# ESP32.net
KiCad netlist of a schematic drawn in Altium Designer
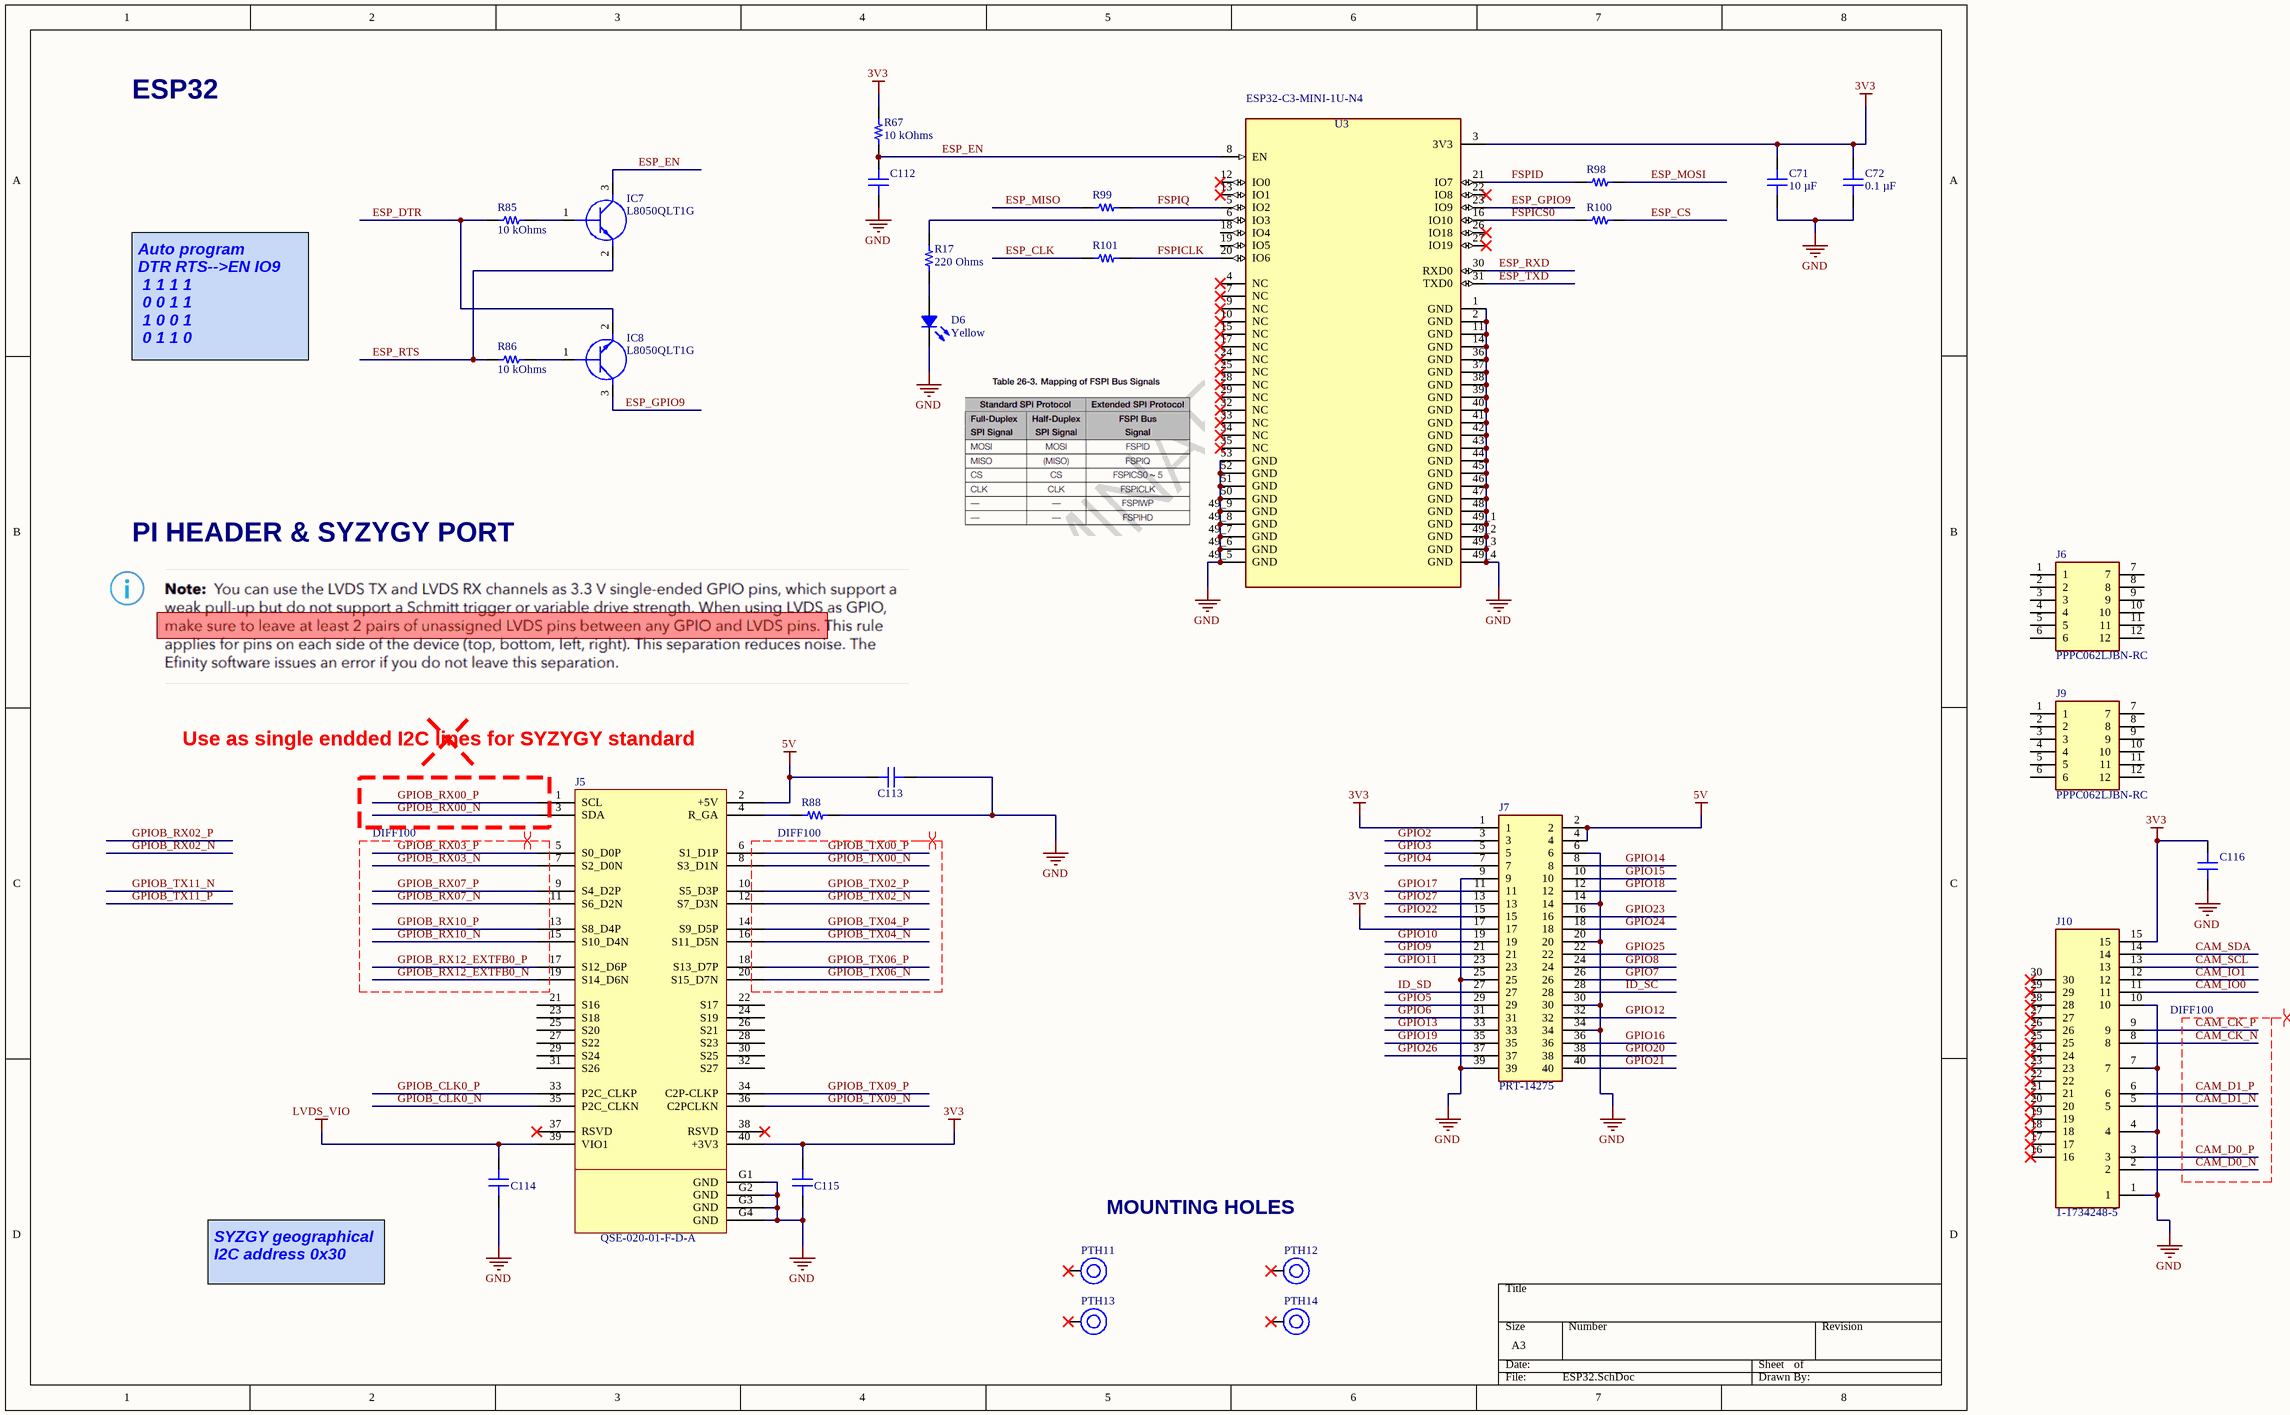
[diagram p0: ESP32.SchDoc]

(export (version "E")
  (design (tool "Eeschema 10.0.6"))
  (components
    (comp (ref "C71")
      (value "10 µF")
      (footprint "CAP 0603_1608")
      (description "CAP CER 10UF 6.3V X5R 0603")
      (fields
        (field (name "PART NUMBER") "GRM188R60J106ME47D")
        (field (name "MANUFACTURER") "Murata Electronics")
      )
      (libsource (lib "Celestial Altium Library - altium_library") (part "Capacitor"))
    )
    (comp (ref "C72")
      (value "0.1 µF")
      (footprint "CAP 0603_1608")
      (description "CAP CER 0.1UF 6.3V X7R 0603")
      (fields
        (field (name "PART NUMBER") "6R3X14W104MV4T")
        (field (name "MANUFACTURER") "Johanson Dielectrics Inc.")
      )
      (libsource (lib "Celestial Altium Library - altium_library") (part "Capacitor"))
    )
    (comp (ref "C112")
      (value "1 µF")
      (footprint "CAP 0402_1005")
      (description "CAP CER 1UF 6.3V X7R 0402")
      (fields
        (field (name "PART NUMBER") "GRM155R70J105KA12J")
        (field (name "MANUFACTURER") "Murata Electronics")
      )
      (libsource (lib "Celestial Altium Library - altium_library") (part "Capacitor"))
    )
    (comp (ref "C113")
      (value "0.1 µF")
      (footprint "CAP 0402_1005")
      (description "CAP CER 0.1UF 10V X7R 0402")
      (fields (field (name "PART NUMBER") "CC0402KRX7R6BB104") (field (name "MANUFACTURER") "Yageo"))
      (libsource (lib "Celestial Altium Library - altium_library") (part "Capacitor"))
    )
    (comp (ref "C114")
      (value "0.1 µF")
      (footprint "CAP 0402_1005")
      (description "CAP CER 0.1UF 10V X7R 0402")
      (fields (field (name "PART NUMBER") "CC0402KRX7R6BB104") (field (name "MANUFACTURER") "Yageo"))
      (libsource (lib "Celestial Altium Library - altium_library") (part "Capacitor"))
    )
    (comp (ref "C115")
      (value "0.1 µF")
      (footprint "CAP 0402_1005")
      (description "CAP CER 0.1UF 10V X7R 0402")
      (fields (field (name "PART NUMBER") "CC0402KRX7R6BB104") (field (name "MANUFACTURER") "Yageo"))
      (libsource (lib "Celestial Altium Library - altium_library") (part "Capacitor"))
    )
    (comp (ref "C116")
      (value "0.1 µF")
      (footprint "CAP 0402_1005")
      (description "CAP CER 0.1UF 10V X7R 0402")
      (fields (field (name "PART NUMBER") "CC0402KRX7R6BB104") (field (name "MANUFACTURER") "Yageo"))
      (libsource (lib "Celestial Altium Library - altium_library") (part "Capacitor"))
    )
    (comp (ref "D6")
      (value "Yellow")
      (footprint "LED 0603_1608 YELLOW")
      (description "LED YELLOW DIFFUSED SMD")
      (fields
        (field (name "PART NUMBER") "SML-LX0603YW-TR")
        (field (name "MANUFACTURER") "Lumex Opto/Components Inc.")
      )
      (libsource (lib "Celestial Altium Library - altium_library") (part "LED"))
    )
    (comp (ref "IC7")
      (value "L8050QLT1G")
      (footprint "SamacSys:L8050QLT1G")
      (description "Integrated Circuit")
      (libsource (lib "SamacSys") (part "L8050QLT1G"))
    )
    (comp (ref "IC8")
      (value "L8050QLT1G")
      (footprint "SamacSys:L8050QLT1G")
      (description "Integrated Circuit")
      (libsource (lib "SamacSys") (part "L8050QLT1G"))
    )
    (comp (ref "J5")
      (value "QSE-020-01-F-D-A")
      (footprint "Components - 26.11.22 - 19.48:QSE-020-01-F-D-A-Footprint-2")
      (description "Conn High Speed Socket Strip SKT 40 POS 0.8mm Solder ST SMD Tray")
      (libsource (lib "Components - 26.11.22 - 19.48") (part "CMP-002-00073-2_2"))
    )
    (comp (ref "J6")
      (value "PPPC062LJBN-RC")
      (footprint "SamacSys:RHDRRA12W60P254X254_2X6_1574X850X508P")
      (description "Connector")
      (libsource (lib "SamacSys") (part "PPPC062LJBN-RC"))
    )
    (comp (ref "J7")
      (value "PRT-14275")
      (footprint "SamacSys:HDRV40W64P254_2X20_5080X500X884P")
      (description "Connector")
      (fields (field (name "MOUSER PART NUMBER") "474-PRT-14275"))
      (libsource (lib "SamacSys") (part "PRT-14275"))
    )
    (comp (ref "J9")
      (value "PPPC062LJBN-RC")
      (footprint "SamacSys:RHDRRA12W60P254X254_2X6_1574X850X508P")
      (description "Connector")
      (libsource (lib "SamacSys") (part "PPPC062LJBN-RC"))
    )
    (comp (ref "J10")
      (value "1-1734248-5")
      (footprint "SamacSys:117342485")
      (description "Connector")
      (fields (field (name "MOUSER PART NUMBER") "571-1-1734248-5"))
      (libsource (lib "SamacSys") (part "1-1734248-5"))
    )
    (comp (ref "PTH11")
      (value "SYZYGY_PCB_Mounting_Hole")
      (footprint "SYZYGY_PCB_Mounting_Hole")
      (libsource (lib "T8_devkit_PCB") (part "SYZYGY_PCB_Mounting_Hole"))
    )
    (comp (ref "PTH12")
      (value "SYZYGY_PCB_Mounting_Hole")
      (footprint "SYZYGY_PCB_Mounting_Hole")
      (libsource (lib "T8_devkit_PCB") (part "SYZYGY_PCB_Mounting_Hole"))
    )
    (comp (ref "PTH13")
      (value "SYZYGY_PCB_Mounting_Hole")
      (footprint "SYZYGY_PCB_Mounting_Hole")
      (libsource (lib "T8_devkit_PCB") (part "SYZYGY_PCB_Mounting_Hole"))
    )
    (comp (ref "PTH14")
      (value "SYZYGY_PCB_Mounting_Hole")
      (footprint "SYZYGY_PCB_Mounting_Hole")
      (libsource (lib "T8_devkit_PCB") (part "SYZYGY_PCB_Mounting_Hole"))
    )
    (comp (ref "R17")
      (value "220 Ohms")
      (footprint "RES 0402_1005")
      (description "RES 220 OHM 1% 1/16W 0402")
      (fields (field (name "PART NUMBER") "RC0402FR-07220RL") (field (name "MANUFACTURER") "Yageo"))
      (libsource (lib "Celestial Altium Library - altium_library") (part "Resistor"))
    )
    (comp (ref "R67")
      (value "10 kOhms")
      (footprint "RES 0402_1005")
      (description "RES 10K OHM 0.1% 1/10W 0402")
      (fields
        (field (name "PART NUMBER") "RP73PF1E10KBTD")
        (field (name "MANUFACTURER") "TE Connectivity Passive Product")
      )
      (libsource (lib "Celestial Altium Library - altium_library") (part "Resistor"))
    )
    (comp (ref "R85")
      (value "10 kOhms")
      (footprint "RES 0402_1005")
      (description "RES 10K OHM 0.1% 1/10W 0402")
      (fields
        (field (name "PART NUMBER") "RP73PF1E10KBTD")
        (field (name "MANUFACTURER") "TE Connectivity Passive Product")
      )
      (libsource (lib "Celestial Altium Library - altium_library") (part "Resistor"))
    )
    (comp (ref "R86")
      (value "10 kOhms")
      (footprint "RES 0402_1005")
      (description "RES 10K OHM 0.1% 1/10W 0402")
      (fields
        (field (name "PART NUMBER") "RP73PF1E10KBTD")
        (field (name "MANUFACTURER") "TE Connectivity Passive Product")
      )
      (libsource (lib "Celestial Altium Library - altium_library") (part "Resistor"))
    )
    (comp (ref "R88")
      (value "210 kOhms")
      (footprint "RES 0402_1005")
      (description "RES 210K OHM 1% 1/16W 0402")
      (fields (field (name "PART NUMBER") "RC0402FR-07210KL") (field (name "MANUFACTURER") "Yageo"))
      (libsource (lib "Celestial Altium Library - altium_library") (part "Resistor"))
    )
    (comp (ref "R98")
      (value "33 Ohms")
      (footprint "RES 0402_1005")
      (description "RES 33 OHM 1% 1/16W 0402")
      (fields (field (name "PART NUMBER") "RC0402FR-0733RL") (field (name "MANUFACTURER") "Yageo"))
      (libsource (lib "Celestial Altium Library - altium_library") (part "Resistor"))
    )
    (comp (ref "R99")
      (value "33 Ohms")
      (footprint "RES 0402_1005")
      (description "RES 33 OHM 1% 1/16W 0402")
      (fields (field (name "PART NUMBER") "RC0402FR-0733RL") (field (name "MANUFACTURER") "Yageo"))
      (libsource (lib "Celestial Altium Library - altium_library") (part "Resistor"))
    )
    (comp (ref "R100")
      (value "33 Ohms")
      (footprint "RES 0402_1005")
      (description "RES 33 OHM 1% 1/16W 0402")
      (fields (field (name "PART NUMBER") "RC0402FR-0733RL") (field (name "MANUFACTURER") "Yageo"))
      (libsource (lib "Celestial Altium Library - altium_library") (part "Resistor"))
    )
    (comp (ref "R101")
      (value "33 Ohms")
      (footprint "RES 0402_1005")
      (description "RES 33 OHM 1% 1/16W 0402")
      (fields (field (name "PART NUMBER") "RC0402FR-0733RL") (field (name "MANUFACTURER") "Yageo"))
      (libsource (lib "Celestial Altium Library - altium_library") (part "Resistor"))
    )
    (comp (ref "U3")
      (value "ESP32-C3-MINI-1U-N4")
      (footprint "XCVR_ESP32-C3-MINI-1U-N4:XCVR_ESP32-C3-MINI-1U-N4")
      (fields
        (field (name "MF") "Espressif Systems")
        (field (name "DIGI-KEY_PART_NUMBER") "1965-ESP32-C3-MINI-1U-N4TR-ND")
      )
      (libsource (lib "ESP32-C3-MINI-1U-N4") (part "ESP32-C3-MINI-1U-N4"))
    )
  )
  (nets
    (net (code "1") (name "/CAM_CK_N") (class "Default")
      (node (ref "J10") (pin "8") (pinfunction "8_8") (pintype "passive"))
    )
    (net (code "2") (name "/CAM_CK_P") (class "Default")
      (node (ref "J10") (pin "9") (pinfunction "9_9") (pintype "passive"))
    )
    (net (code "3") (name "/CAM_D0_N") (class "Default")
      (node (ref "J10") (pin "2") (pinfunction "2_2") (pintype "passive"))
    )
    (net (code "4") (name "/CAM_D0_P") (class "Default")
      (node (ref "J10") (pin "3") (pinfunction "3_3") (pintype "passive"))
    )
    (net (code "5") (name "/CAM_D1_N") (class "Default")
      (node (ref "J10") (pin "5") (pinfunction "5_5") (pintype "passive"))
    )
    (net (code "6") (name "/CAM_D1_P") (class "Default")
      (node (ref "J10") (pin "6") (pinfunction "6_6") (pintype "passive"))
    )
    (net (code "7") (name "/CAM_IO0") (class "Default")
      (node (ref "J10") (pin "11") (pinfunction "11_11") (pintype "passive"))
    )
    (net (code "8") (name "/CAM_IO1") (class "Default")
      (node (ref "J10") (pin "12") (pinfunction "12_12") (pintype "passive"))
    )
    (net (code "9") (name "/CAM_SCL") (class "Default")
      (node (ref "J10") (pin "13") (pinfunction "13_13") (pintype "passive"))
    )
    (net (code "10") (name "/CAM_SDA") (class "Default")
      (node (ref "J10") (pin "14") (pinfunction "14_14") (pintype "passive"))
    )
    (net (code "11") (name "/ESP_CLK") (class "Default")
      (node (ref "R101") (pin "1") (pinfunction "1_1") (pintype "passive"))
    )
    (net (code "12") (name "/ESP_CS") (class "Default")
      (node (ref "R100") (pin "2") (pinfunction "2_2") (pintype "passive"))
    )
    (net (code "13") (name "/ESP_DTR") (class "Default")
      (node (ref "IC8") (pin "2") (pinfunction "E_2") (pintype "passive"))
      (node (ref "R85") (pin "2") (pinfunction "2_2") (pintype "passive"))
    )
    (net (code "14") (name "/ESP_EN") (class "Default")
      (node (ref "C112") (pin "2") (pinfunction "2_2") (pintype "passive"))
      (node (ref "IC7") (pin "3") (pinfunction "C_3") (pintype "passive"))
      (node (ref "R67") (pin "1") (pinfunction "1_1") (pintype "passive"))
      (node (ref "U3") (pin "8") (pinfunction "EN_8") (pintype "input"))
    )
    (net (code "15") (name "/ESP_GPIO9") (class "Default")
      (node (ref "IC8") (pin "3") (pinfunction "C_3") (pintype "passive"))
      (node (ref "U3") (pin "23") (pinfunction "IO9_23") (pintype "bidirectional"))
    )
    (net (code "16") (name "/ESP_MISO") (class "Default")
      (node (ref "R99") (pin "1") (pinfunction "1_1") (pintype "passive"))
    )
    (net (code "17") (name "/ESP_MOSI") (class "Default")
      (node (ref "R98") (pin "2") (pinfunction "2_2") (pintype "passive"))
    )
    (net (code "18") (name "/ESP_RTS") (class "Default")
      (node (ref "IC7") (pin "2") (pinfunction "E_2") (pintype "passive"))
      (node (ref "R86") (pin "2") (pinfunction "2_2") (pintype "passive"))
    )
    (net (code "19") (name "/ESP_RXD") (class "Default")
      (node (ref "U3") (pin "30") (pinfunction "RXD0_30") (pintype "bidirectional"))
    )
    (net (code "20") (name "/ESP_TXD") (class "Default")
      (node (ref "U3") (pin "31") (pinfunction "TXD0_31") (pintype "bidirectional"))
    )
    (net (code "21") (name "/FSPICLK") (class "Default")
      (node (ref "R101") (pin "2") (pinfunction "2_2") (pintype "passive"))
      (node (ref "U3") (pin "20") (pinfunction "IO6_20") (pintype "bidirectional"))
    )
    (net (code "22") (name "/FSPICS0") (class "Default")
      (node (ref "R100") (pin "1") (pinfunction "1_1") (pintype "passive"))
      (node (ref "U3") (pin "16") (pinfunction "IO10_16") (pintype "bidirectional"))
    )
    (net (code "23") (name "/FSPID") (class "Default")
      (node (ref "R98") (pin "1") (pinfunction "1_1") (pintype "passive"))
      (node (ref "U3") (pin "21") (pinfunction "IO7_21") (pintype "bidirectional"))
    )
    (net (code "24") (name "/FSPIQ") (class "Default")
      (node (ref "R99") (pin "2") (pinfunction "2_2") (pintype "passive"))
      (node (ref "U3") (pin "5") (pinfunction "IO2_5") (pintype "bidirectional"))
    )
    (net (code "25") (name "/GPIO2") (class "Default")
      (node (ref "J7") (pin "3") (pinfunction "3_3") (pintype "passive"))
    )
    (net (code "26") (name "/GPIO3") (class "Default")
      (node (ref "J7") (pin "5") (pinfunction "5_5") (pintype "passive"))
    )
    (net (code "27") (name "/GPIO4") (class "Default")
      (node (ref "J7") (pin "7") (pinfunction "7_7") (pintype "passive"))
    )
    (net (code "28") (name "/GPIO5") (class "Default")
      (node (ref "J7") (pin "29") (pinfunction "29_29") (pintype "passive"))
    )
    (net (code "29") (name "/GPIO6") (class "Default")
      (node (ref "J7") (pin "31") (pinfunction "31_31") (pintype "passive"))
    )
    (net (code "30") (name "/GPIO7") (class "Default")
      (node (ref "J7") (pin "26") (pinfunction "26_26") (pintype "passive"))
    )
    (net (code "31") (name "/GPIO8") (class "Default")
      (node (ref "J7") (pin "24") (pinfunction "24_24") (pintype "passive"))
    )
    (net (code "32") (name "/GPIO9") (class "Default")
      (node (ref "J7") (pin "21") (pinfunction "21_21") (pintype "passive"))
    )
    (net (code "33") (name "/GPIO10") (class "Default")
      (node (ref "J7") (pin "19") (pinfunction "19_19") (pintype "passive"))
    )
    (net (code "34") (name "/GPIO11") (class "Default")
      (node (ref "J7") (pin "23") (pinfunction "23_23") (pintype "passive"))
    )
    (net (code "35") (name "/GPIO12") (class "Default")
      (node (ref "J7") (pin "32") (pinfunction "32_32") (pintype "passive"))
    )
    (net (code "36") (name "/GPIO13") (class "Default")
      (node (ref "J7") (pin "33") (pinfunction "33_33") (pintype "passive"))
    )
    (net (code "37") (name "/GPIO14") (class "Default")
      (node (ref "J7") (pin "8") (pinfunction "8_8") (pintype "passive"))
    )
    (net (code "38") (name "/GPIO15") (class "Default")
      (node (ref "J7") (pin "10") (pinfunction "10_10") (pintype "passive"))
    )
    (net (code "39") (name "/GPIO16") (class "Default")
      (node (ref "J7") (pin "36") (pinfunction "36_36") (pintype "passive"))
    )
    (net (code "40") (name "/GPIO17") (class "Default")
      (node (ref "J7") (pin "11") (pinfunction "11_11") (pintype "passive"))
    )
    (net (code "41") (name "/GPIO18") (class "Default")
      (node (ref "J7") (pin "12") (pinfunction "12_12") (pintype "passive"))
    )
    (net (code "42") (name "/GPIO19") (class "Default")
      (node (ref "J7") (pin "35") (pinfunction "35_35") (pintype "passive"))
    )
    (net (code "43") (name "/GPIO20") (class "Default")
      (node (ref "J7") (pin "38") (pinfunction "38_38") (pintype "passive"))
    )
    (net (code "44") (name "/GPIO21") (class "Default")
      (node (ref "J7") (pin "40") (pinfunction "40_40") (pintype "passive"))
    )
    (net (code "45") (name "/GPIO22") (class "Default")
      (node (ref "J7") (pin "15") (pinfunction "15_15") (pintype "passive"))
    )
    (net (code "46") (name "/GPIO23") (class "Default")
      (node (ref "J7") (pin "16") (pinfunction "16_16") (pintype "passive"))
    )
    (net (code "47") (name "/GPIO24") (class "Default")
      (node (ref "J7") (pin "18") (pinfunction "18_18") (pintype "passive"))
    )
    (net (code "48") (name "/GPIO25") (class "Default")
      (node (ref "J7") (pin "22") (pinfunction "22_22") (pintype "passive"))
    )
    (net (code "49") (name "/GPIO26") (class "Default")
      (node (ref "J7") (pin "37") (pinfunction "37_37") (pintype "passive"))
    )
    (net (code "50") (name "/GPIO27") (class "Default")
      (node (ref "J7") (pin "13") (pinfunction "13_13") (pintype "passive"))
    )
    (net (code "51") (name "/GPIOB_CLK0_N") (class "Default")
      (node (ref "J5") (pin "35") (pinfunction "P2C_CLKN_35") (pintype "passive"))
    )
    (net (code "52") (name "/GPIOB_CLK0_P") (class "Default")
      (node (ref "J5") (pin "33") (pinfunction "P2C_CLKP_33") (pintype "passive"))
    )
    (net (code "53") (name "/GPIOB_RX00_N") (class "Default")
      (node (ref "J5") (pin "3") (pinfunction "SDA_3") (pintype "passive"))
    )
    (net (code "54") (name "/GPIOB_RX00_P") (class "Default")
      (node (ref "J5") (pin "1") (pinfunction "SCL_1") (pintype "passive"))
    )
    (net (code "57") (name "/GPIOB_RX03_N") (class "Default")
      (node (ref "J5") (pin "7") (pinfunction "S2_D0N_7") (pintype "passive"))
    )
    (net (code "58") (name "/GPIOB_RX03_P") (class "Default")
      (node (ref "J5") (pin "5") (pinfunction "S0_D0P_5") (pintype "passive"))
    )
    (net (code "59") (name "/GPIOB_RX07_N") (class "Default")
      (node (ref "J5") (pin "11") (pinfunction "S6_D2N_11") (pintype "passive"))
    )
    (net (code "60") (name "/GPIOB_RX07_P") (class "Default")
      (node (ref "J5") (pin "9") (pinfunction "S4_D2P_9") (pintype "passive"))
    )
    (net (code "61") (name "/GPIOB_RX10_N") (class "Default")
      (node (ref "J5") (pin "15") (pinfunction "S10_D4N_15") (pintype "passive"))
    )
    (net (code "62") (name "/GPIOB_RX10_P") (class "Default")
      (node (ref "J5") (pin "13") (pinfunction "S8_D4P_13") (pintype "passive"))
    )
    (net (code "63") (name "/GPIOB_RX12_EXTFB0_N") (class "Default")
      (node (ref "J5") (pin "19") (pinfunction "S14_D6N_19") (pintype "passive"))
    )
    (net (code "64") (name "/GPIOB_RX12_EXTFB0_P") (class "Default")
      (node (ref "J5") (pin "17") (pinfunction "S12_D6P_17") (pintype "passive"))
    )
    (net (code "65") (name "/GPIOB_TX00_N") (class "Default")
      (node (ref "J5") (pin "8") (pinfunction "S3_D1N_8") (pintype "passive"))
    )
    (net (code "66") (name "/GPIOB_TX00_P") (class "Default")
      (node (ref "J5") (pin "6") (pinfunction "S1_D1P_6") (pintype "passive"))
    )
    (net (code "67") (name "/GPIOB_TX02_N") (class "Default")
      (node (ref "J5") (pin "12") (pinfunction "S7_D3N_12") (pintype "passive"))
    )
    (net (code "68") (name "/GPIOB_TX02_P") (class "Default")
      (node (ref "J5") (pin "10") (pinfunction "S5_D3P_10") (pintype "passive"))
    )
    (net (code "69") (name "/GPIOB_TX04_N") (class "Default")
      (node (ref "J5") (pin "16") (pinfunction "S11_D5N_16") (pintype "passive"))
    )
    (net (code "70") (name "/GPIOB_TX04_P") (class "Default")
      (node (ref "J5") (pin "14") (pinfunction "S9_D5P_14") (pintype "passive"))
    )
    (net (code "71") (name "/GPIOB_TX06_N") (class "Default")
      (node (ref "J5") (pin "20") (pinfunction "S15_D7N_20") (pintype "passive"))
    )
    (net (code "72") (name "/GPIOB_TX06_P") (class "Default")
      (node (ref "J5") (pin "18") (pinfunction "S13_D7P_18") (pintype "passive"))
    )
    (net (code "73") (name "/GPIOB_TX09_N") (class "Default")
      (node (ref "J5") (pin "36") (pinfunction "C2PCLKN_36") (pintype "passive"))
    )
    (net (code "74") (name "/GPIOB_TX09_P") (class "Default")
      (node (ref "J5") (pin "34") (pinfunction "C2P-CLKP_34") (pintype "passive"))
    )
    (net (code "77") (name "/ID_SC") (class "Default")
      (node (ref "J7") (pin "28") (pinfunction "28_28") (pintype "passive"))
    )
    (net (code "78") (name "/ID_SD") (class "Default")
      (node (ref "J7") (pin "27") (pinfunction "27_27") (pintype "passive"))
    )
    (net (code "79") (name "3V3") (class "Default")
      (node (ref "C115") (pin "1") (pinfunction "1_1") (pintype "passive"))
      (node (ref "C116") (pin "2") (pinfunction "2_2") (pintype "passive"))
      (node (ref "C71") (pin "2") (pinfunction "2_2") (pintype "passive"))
      (node (ref "C72") (pin "2") (pinfunction "2_2") (pintype "passive"))
      (node (ref "J10") (pin "15") (pinfunction "15_15") (pintype "passive"))
      (node (ref "J5") (pin "40") (pinfunction "+3V3_40") (pintype "passive"))
      (node (ref "J7") (pin "1") (pinfunction "1_1") (pintype "passive"))
      (node (ref "J7") (pin "17") (pinfunction "17_17") (pintype "passive"))
      (node (ref "R67") (pin "2") (pinfunction "2_2") (pintype "passive"))
      (node (ref "U3") (pin "3") (pinfunction "3V3_3") (pintype "power_in"))
    )
    (net (code "80") (name "5V") (class "Default")
      (node (ref "C113") (pin "2") (pinfunction "2_2") (pintype "passive"))
      (node (ref "J5") (pin "2") (pinfunction "+5V_2") (pintype "passive"))
      (node (ref "J7") (pin "2") (pinfunction "2_2") (pintype "passive"))
      (node (ref "J7") (pin "4") (pinfunction "4_4") (pintype "passive"))
    )
    (net (code "81") (name "GND") (class "Default")
      (node (ref "C112") (pin "1") (pinfunction "1_1") (pintype "passive"))
      (node (ref "C113") (pin "1") (pinfunction "1_1") (pintype "passive"))
      (node (ref "C114") (pin "2") (pinfunction "2_2") (pintype "passive"))
      (node (ref "C115") (pin "2") (pinfunction "2_2") (pintype "passive"))
      (node (ref "C116") (pin "1") (pinfunction "1_1") (pintype "passive"))
      (node (ref "C71") (pin "1") (pinfunction "1_1") (pintype "passive"))
      (node (ref "C72") (pin "1") (pinfunction "1_1") (pintype "passive"))
      (node (ref "D6") (pin "2") (pinfunction "2_2") (pintype "passive"))
      (node (ref "J10") (pin "1") (pinfunction "1_1") (pintype "passive"))
      (node (ref "J10") (pin "10") (pinfunction "10_10") (pintype "passive"))
      (node (ref "J10") (pin "4") (pinfunction "4_4") (pintype "passive"))
      (node (ref "J10") (pin "7") (pinfunction "7_7") (pintype "passive"))
      (node (ref "J5") (pin "G1") (pinfunction "GND_G1") (pintype "power_in"))
      (node (ref "J5") (pin "G2") (pinfunction "GND_G2") (pintype "power_in"))
      (node (ref "J5") (pin "G3") (pinfunction "GND_G3") (pintype "power_in"))
      (node (ref "J5") (pin "G4") (pinfunction "GND_G4") (pintype "power_in"))
      (node (ref "J7") (pin "14") (pinfunction "14_14") (pintype "passive"))
      (node (ref "J7") (pin "20") (pinfunction "20_20") (pintype "passive"))
      (node (ref "J7") (pin "25") (pinfunction "25_25") (pintype "passive"))
      (node (ref "J7") (pin "30") (pinfunction "30_30") (pintype "passive"))
      (node (ref "J7") (pin "34") (pinfunction "34_34") (pintype "passive"))
      (node (ref "J7") (pin "39") (pinfunction "39_39") (pintype "passive"))
      (node (ref "J7") (pin "6") (pinfunction "6_6") (pintype "passive"))
      (node (ref "J7") (pin "9") (pinfunction "9_9") (pintype "passive"))
      (node (ref "R88") (pin "2") (pinfunction "2_2") (pintype "passive"))
      (node (ref "U3") (pin "1") (pinfunction "GND_1") (pintype "power_in"))
      (node (ref "U3") (pin "11") (pinfunction "GND_11") (pintype "power_in"))
      (node (ref "U3") (pin "14") (pinfunction "GND_14") (pintype "power_in"))
      (node (ref "U3") (pin "2") (pinfunction "GND_2") (pintype "power_in"))
      (node (ref "U3") (pin "36") (pinfunction "GND_36") (pintype "power_in"))
      (node (ref "U3") (pin "37") (pinfunction "GND_37") (pintype "power_in"))
      (node (ref "U3") (pin "38") (pinfunction "GND_38") (pintype "power_in"))
      (node (ref "U3") (pin "39") (pinfunction "GND_39") (pintype "power_in"))
      (node (ref "U3") (pin "40") (pinfunction "GND_40") (pintype "power_in"))
      (node (ref "U3") (pin "41") (pinfunction "GND_41") (pintype "power_in"))
      (node (ref "U3") (pin "42") (pinfunction "GND_42") (pintype "power_in"))
      (node (ref "U3") (pin "43") (pinfunction "GND_43") (pintype "power_in"))
      (node (ref "U3") (pin "44") (pinfunction "GND_44") (pintype "power_in"))
      (node (ref "U3") (pin "45") (pinfunction "GND_45") (pintype "power_in"))
      (node (ref "U3") (pin "46") (pinfunction "GND_46") (pintype "power_in"))
      (node (ref "U3") (pin "47") (pinfunction "GND_47") (pintype "power_in"))
      (node (ref "U3") (pin "48") (pinfunction "GND_48") (pintype "power_in"))
      (node (ref "U3") (pin "49_1") (pinfunction "GND_49_1") (pintype "power_in"))
      (node (ref "U3") (pin "49_2") (pinfunction "GND_49_2") (pintype "power_in"))
      (node (ref "U3") (pin "49_3") (pinfunction "GND_49_3") (pintype "power_in"))
      (node (ref "U3") (pin "49_4") (pinfunction "GND_49_4") (pintype "power_in"))
      (node (ref "U3") (pin "49_5") (pinfunction "GND_49_5") (pintype "power_in"))
      (node (ref "U3") (pin "49_6") (pinfunction "GND_49_6") (pintype "power_in"))
      (node (ref "U3") (pin "49_7") (pinfunction "GND_49_7") (pintype "power_in"))
      (node (ref "U3") (pin "49_8") (pinfunction "GND_49_8") (pintype "power_in"))
      (node (ref "U3") (pin "49_9") (pinfunction "GND_49_9") (pintype "power_in"))
      (node (ref "U3") (pin "50") (pinfunction "GND_50") (pintype "power_in"))
      (node (ref "U3") (pin "51") (pinfunction "GND_51") (pintype "power_in"))
      (node (ref "U3") (pin "52") (pinfunction "GND_52") (pintype "power_in"))
      (node (ref "U3") (pin "53") (pinfunction "GND_53") (pintype "power_in"))
    )
    (net (code "82") (name "LVDS_VIO") (class "Default")
      (node (ref "C114") (pin "1") (pinfunction "1_1") (pintype "passive"))
      (node (ref "J5") (pin "39") (pinfunction "VIO1_39") (pintype "passive"))
    )
    (net (code "83") (name "Net-(D6-Pad1)") (class "Default")
      (node (ref "D6") (pin "1") (pinfunction "1_1") (pintype "passive"))
      (node (ref "R17") (pin "2") (pinfunction "2_2") (pintype "passive"))
    )
    (net (code "84") (name "Net-(IC7-B)") (class "Default")
      (node (ref "IC7") (pin "1") (pinfunction "B_1") (pintype "passive"))
      (node (ref "R85") (pin "1") (pinfunction "1_1") (pintype "passive"))
    )
    (net (code "85") (name "Net-(IC8-B)") (class "Default")
      (node (ref "IC8") (pin "1") (pinfunction "B_1") (pintype "passive"))
      (node (ref "R86") (pin "1") (pinfunction "1_1") (pintype "passive"))
    )
    (net (code "86") (name "Net-(J5-R_GA)") (class "Default")
      (node (ref "J5") (pin "4") (pinfunction "R_GA_4") (pintype "passive"))
      (node (ref "R88") (pin "1") (pinfunction "1_1") (pintype "passive"))
    )
    (net (code "87") (name "Net-(U3-IO3)") (class "Default")
      (node (ref "R17") (pin "1") (pinfunction "1_1") (pintype "passive"))
      (node (ref "U3") (pin "6") (pinfunction "IO3_6") (pintype "bidirectional"))
    )
    (net (code "88") (name "unconnected-(J5-RSVD-Pad37)") (class "Default")
      (node (ref "J5") (pin "37") (pinfunction "RSVD_37") (pintype "passive+no_connect"))
    )
    (net (code "89") (name "unconnected-(J5-RSVD-Pad38)") (class "Default")
      (node (ref "J5") (pin "38") (pinfunction "RSVD_38") (pintype "passive+no_connect"))
    )
    (net (code "90") (name "unconnected-(J5-S16-Pad21)") (class "Default")
      (node (ref "J5") (pin "21") (pinfunction "S16_21") (pintype "passive"))
    )
    (net (code "91") (name "unconnected-(J5-S17-Pad22)") (class "Default")
      (node (ref "J5") (pin "22") (pinfunction "S17_22") (pintype "passive"))
    )
    (net (code "92") (name "unconnected-(J5-S18-Pad23)") (class "Default")
      (node (ref "J5") (pin "23") (pinfunction "S18_23") (pintype "passive"))
    )
    (net (code "93") (name "unconnected-(J5-S19-Pad24)") (class "Default")
      (node (ref "J5") (pin "24") (pinfunction "S19_24") (pintype "passive"))
    )
    (net (code "94") (name "unconnected-(J5-S20-Pad25)") (class "Default")
      (node (ref "J5") (pin "25") (pinfunction "S20_25") (pintype "passive"))
    )
    (net (code "95") (name "unconnected-(J5-S21-Pad26)") (class "Default")
      (node (ref "J5") (pin "26") (pinfunction "S21_26") (pintype "passive"))
    )
    (net (code "96") (name "unconnected-(J5-S22-Pad27)") (class "Default")
      (node (ref "J5") (pin "27") (pinfunction "S22_27") (pintype "passive"))
    )
    (net (code "97") (name "unconnected-(J5-S23-Pad28)") (class "Default")
      (node (ref "J5") (pin "28") (pinfunction "S23_28") (pintype "passive"))
    )
    (net (code "98") (name "unconnected-(J5-S24-Pad29)") (class "Default")
      (node (ref "J5") (pin "29") (pinfunction "S24_29") (pintype "passive"))
    )
    (net (code "99") (name "unconnected-(J5-S25-Pad30)") (class "Default")
      (node (ref "J5") (pin "30") (pinfunction "S25_30") (pintype "passive"))
    )
    (net (code "100") (name "unconnected-(J5-S26-Pad31)") (class "Default")
      (node (ref "J5") (pin "31") (pinfunction "S26_31") (pintype "passive"))
    )
    (net (code "101") (name "unconnected-(J5-S27-Pad32)") (class "Default")
      (node (ref "J5") (pin "32") (pinfunction "S27_32") (pintype "passive"))
    )
    (net (code "102") (name "unconnected-(J6-Pad1)") (class "Default")
      (node (ref "J6") (pin "1") (pinfunction "1_1") (pintype "passive"))
    )
    (net (code "103") (name "unconnected-(J6-Pad2)") (class "Default")
      (node (ref "J6") (pin "2") (pinfunction "2_2") (pintype "passive"))
    )
    (net (code "104") (name "unconnected-(J6-Pad3)") (class "Default")
      (node (ref "J6") (pin "3") (pinfunction "3_3") (pintype "passive"))
    )
    (net (code "105") (name "unconnected-(J6-Pad4)") (class "Default")
      (node (ref "J6") (pin "4") (pinfunction "4_4") (pintype "passive"))
    )
    (net (code "106") (name "unconnected-(J6-Pad5)") (class "Default")
      (node (ref "J6") (pin "5") (pinfunction "5_5") (pintype "passive"))
    )
    (net (code "107") (name "unconnected-(J6-Pad6)") (class "Default")
      (node (ref "J6") (pin "6") (pinfunction "6_6") (pintype "passive"))
    )
    (net (code "108") (name "unconnected-(J6-Pad7)") (class "Default")
      (node (ref "J6") (pin "7") (pinfunction "7_7") (pintype "passive"))
    )
    (net (code "109") (name "unconnected-(J6-Pad8)") (class "Default")
      (node (ref "J6") (pin "8") (pinfunction "8_8") (pintype "passive"))
    )
    (net (code "110") (name "unconnected-(J6-Pad9)") (class "Default")
      (node (ref "J6") (pin "9") (pinfunction "9_9") (pintype "passive"))
    )
    (net (code "111") (name "unconnected-(J6-Pad10)") (class "Default")
      (node (ref "J6") (pin "10") (pinfunction "10_10") (pintype "passive"))
    )
    (net (code "112") (name "unconnected-(J6-Pad11)") (class "Default")
      (node (ref "J6") (pin "11") (pinfunction "11_11") (pintype "passive"))
    )
    (net (code "113") (name "unconnected-(J6-Pad12)") (class "Default")
      (node (ref "J6") (pin "12") (pinfunction "12_12") (pintype "passive"))
    )
    (net (code "114") (name "unconnected-(J9-Pad1)") (class "Default")
      (node (ref "J9") (pin "1") (pinfunction "1_1") (pintype "passive"))
    )
    (net (code "115") (name "unconnected-(J9-Pad2)") (class "Default")
      (node (ref "J9") (pin "2") (pinfunction "2_2") (pintype "passive"))
    )
    (net (code "116") (name "unconnected-(J9-Pad3)") (class "Default")
      (node (ref "J9") (pin "3") (pinfunction "3_3") (pintype "passive"))
    )
    (net (code "117") (name "unconnected-(J9-Pad4)") (class "Default")
      (node (ref "J9") (pin "4") (pinfunction "4_4") (pintype "passive"))
    )
    (net (code "118") (name "unconnected-(J9-Pad5)") (class "Default")
      (node (ref "J9") (pin "5") (pinfunction "5_5") (pintype "passive"))
    )
    (net (code "119") (name "unconnected-(J9-Pad6)") (class "Default")
      (node (ref "J9") (pin "6") (pinfunction "6_6") (pintype "passive"))
    )
    (net (code "120") (name "unconnected-(J9-Pad7)") (class "Default")
      (node (ref "J9") (pin "7") (pinfunction "7_7") (pintype "passive"))
    )
    (net (code "121") (name "unconnected-(J9-Pad8)") (class "Default")
      (node (ref "J9") (pin "8") (pinfunction "8_8") (pintype "passive"))
    )
    (net (code "122") (name "unconnected-(J9-Pad9)") (class "Default")
      (node (ref "J9") (pin "9") (pinfunction "9_9") (pintype "passive"))
    )
    (net (code "123") (name "unconnected-(J9-Pad10)") (class "Default")
      (node (ref "J9") (pin "10") (pinfunction "10_10") (pintype "passive"))
    )
    (net (code "124") (name "unconnected-(J9-Pad11)") (class "Default")
      (node (ref "J9") (pin "11") (pinfunction "11_11") (pintype "passive"))
    )
    (net (code "125") (name "unconnected-(J9-Pad12)") (class "Default")
      (node (ref "J9") (pin "12") (pinfunction "12_12") (pintype "passive"))
    )
    (net (code "126") (name "unconnected-(J10-Pad16)") (class "Default")
      (node (ref "J10") (pin "16") (pinfunction "16_16") (pintype "passive+no_connect"))
    )
    (net (code "127") (name "unconnected-(J10-Pad17)") (class "Default")
      (node (ref "J10") (pin "17") (pinfunction "17_17") (pintype "passive+no_connect"))
    )
    (net (code "128") (name "unconnected-(J10-Pad18)") (class "Default")
      (node (ref "J10") (pin "18") (pinfunction "18_18") (pintype "passive+no_connect"))
    )
    (net (code "129") (name "unconnected-(J10-Pad19)") (class "Default")
      (node (ref "J10") (pin "19") (pinfunction "19_19") (pintype "passive+no_connect"))
    )
    (net (code "130") (name "unconnected-(J10-Pad20)") (class "Default")
      (node (ref "J10") (pin "20") (pinfunction "20_20") (pintype "passive+no_connect"))
    )
    (net (code "131") (name "unconnected-(J10-Pad21)") (class "Default")
      (node (ref "J10") (pin "21") (pinfunction "21_21") (pintype "passive+no_connect"))
    )
    (net (code "132") (name "unconnected-(J10-Pad22)") (class "Default")
      (node (ref "J10") (pin "22") (pinfunction "22_22") (pintype "passive+no_connect"))
    )
    (net (code "133") (name "unconnected-(J10-Pad23)") (class "Default")
      (node (ref "J10") (pin "23") (pinfunction "23_23") (pintype "passive+no_connect"))
    )
    (net (code "134") (name "unconnected-(J10-Pad24)") (class "Default")
      (node (ref "J10") (pin "24") (pinfunction "24_24") (pintype "passive+no_connect"))
    )
    (net (code "135") (name "unconnected-(J10-Pad25)") (class "Default")
      (node (ref "J10") (pin "25") (pinfunction "25_25") (pintype "passive+no_connect"))
    )
    (net (code "136") (name "unconnected-(J10-Pad26)") (class "Default")
      (node (ref "J10") (pin "26") (pinfunction "26_26") (pintype "passive+no_connect"))
    )
    (net (code "137") (name "unconnected-(J10-Pad27)") (class "Default")
      (node (ref "J10") (pin "27") (pinfunction "27_27") (pintype "passive+no_connect"))
    )
    (net (code "138") (name "unconnected-(J10-Pad28)") (class "Default")
      (node (ref "J10") (pin "28") (pinfunction "28_28") (pintype "passive+no_connect"))
    )
    (net (code "139") (name "unconnected-(J10-Pad29)") (class "Default")
      (node (ref "J10") (pin "29") (pinfunction "29_29") (pintype "passive+no_connect"))
    )
    (net (code "140") (name "unconnected-(J10-Pad30)") (class "Default")
      (node (ref "J10") (pin "30") (pinfunction "30_30") (pintype "passive+no_connect"))
    )
    (net (code "141") (name "unconnected-(PTH11-Pad1)") (class "Default")
      (node (ref "PTH11") (pin "1") (pinfunction "1_1") (pintype "passive+no_connect"))
    )
    (net (code "142") (name "unconnected-(PTH12-Pad1)") (class "Default")
      (node (ref "PTH12") (pin "1") (pinfunction "1_1") (pintype "passive+no_connect"))
    )
    (net (code "143") (name "unconnected-(PTH13-Pad1)") (class "Default")
      (node (ref "PTH13") (pin "1") (pinfunction "1_1") (pintype "passive+no_connect"))
    )
    (net (code "144") (name "unconnected-(PTH14-Pad1)") (class "Default")
      (node (ref "PTH14") (pin "1") (pinfunction "1_1") (pintype "passive+no_connect"))
    )
    (net (code "145") (name "unconnected-(U3-IO0-Pad12)") (class "Default")
      (node (ref "U3") (pin "12") (pinfunction "IO0_12") (pintype "bidirectional+no_connect"))
    )
    (net (code "146") (name "unconnected-(U3-IO1-Pad13)") (class "Default")
      (node (ref "U3") (pin "13") (pinfunction "IO1_13") (pintype "bidirectional+no_connect"))
    )
    (net (code "147") (name "unconnected-(U3-IO4-Pad18)") (class "Default")
      (node (ref "U3") (pin "18") (pinfunction "IO4_18") (pintype "bidirectional"))
    )
    (net (code "148") (name "unconnected-(U3-IO5-Pad19)") (class "Default")
      (node (ref "U3") (pin "19") (pinfunction "IO5_19") (pintype "bidirectional"))
    )
    (net (code "149") (name "unconnected-(U3-IO8-Pad22)") (class "Default")
      (node (ref "U3") (pin "22") (pinfunction "IO8_22") (pintype "bidirectional+no_connect"))
    )
    (net (code "150") (name "unconnected-(U3-IO18-Pad26)") (class "Default")
      (node (ref "U3") (pin "26") (pinfunction "IO18_26") (pintype "bidirectional+no_connect"))
    )
    (net (code "151") (name "unconnected-(U3-IO19-Pad27)") (class "Default")
      (node (ref "U3") (pin "27") (pinfunction "IO19_27") (pintype "bidirectional+no_connect"))
    )
    (net (code "152") (name "unconnected-(U3-NC-Pad4)") (class "Default")
      (node (ref "U3") (pin "4") (pinfunction "NC_4") (pintype "passive+no_connect"))
    )
    (net (code "153") (name "unconnected-(U3-NC-Pad7)") (class "Default")
      (node (ref "U3") (pin "7") (pinfunction "NC_7") (pintype "passive+no_connect"))
    )
    (net (code "154") (name "unconnected-(U3-NC-Pad9)") (class "Default")
      (node (ref "U3") (pin "9") (pinfunction "NC_9") (pintype "passive+no_connect"))
    )
    (net (code "155") (name "unconnected-(U3-NC-Pad10)") (class "Default")
      (node (ref "U3") (pin "10") (pinfunction "NC_10") (pintype "passive+no_connect"))
    )
    (net (code "156") (name "unconnected-(U3-NC-Pad15)") (class "Default")
      (node (ref "U3") (pin "15") (pinfunction "NC_15") (pintype "passive+no_connect"))
    )
    (net (code "157") (name "unconnected-(U3-NC-Pad17)") (class "Default")
      (node (ref "U3") (pin "17") (pinfunction "NC_17") (pintype "passive+no_connect"))
    )
    (net (code "158") (name "unconnected-(U3-NC-Pad24)") (class "Default")
      (node (ref "U3") (pin "24") (pinfunction "NC_24") (pintype "passive+no_connect"))
    )
    (net (code "159") (name "unconnected-(U3-NC-Pad25)") (class "Default")
      (node (ref "U3") (pin "25") (pinfunction "NC_25") (pintype "passive+no_connect"))
    )
    (net (code "160") (name "unconnected-(U3-NC-Pad28)") (class "Default")
      (node (ref "U3") (pin "28") (pinfunction "NC_28") (pintype "passive+no_connect"))
    )
    (net (code "161") (name "unconnected-(U3-NC-Pad29)") (class "Default")
      (node (ref "U3") (pin "29") (pinfunction "NC_29") (pintype "passive+no_connect"))
    )
    (net (code "162") (name "unconnected-(U3-NC-Pad32)") (class "Default")
      (node (ref "U3") (pin "32") (pinfunction "NC_32") (pintype "passive+no_connect"))
    )
    (net (code "163") (name "unconnected-(U3-NC-Pad33)") (class "Default")
      (node (ref "U3") (pin "33") (pinfunction "NC_33") (pintype "passive+no_connect"))
    )
    (net (code "164") (name "unconnected-(U3-NC-Pad34)") (class "Default")
      (node (ref "U3") (pin "34") (pinfunction "NC_34") (pintype "passive+no_connect"))
    )
    (net (code "165") (name "unconnected-(U3-NC-Pad35)") (class "Default")
      (node (ref "U3") (pin "35") (pinfunction "NC_35") (pintype "passive+no_connect"))
    )
  )
)
